# Dashboardtest.net
KiCad netlist of a schematic drawn in EAGLE
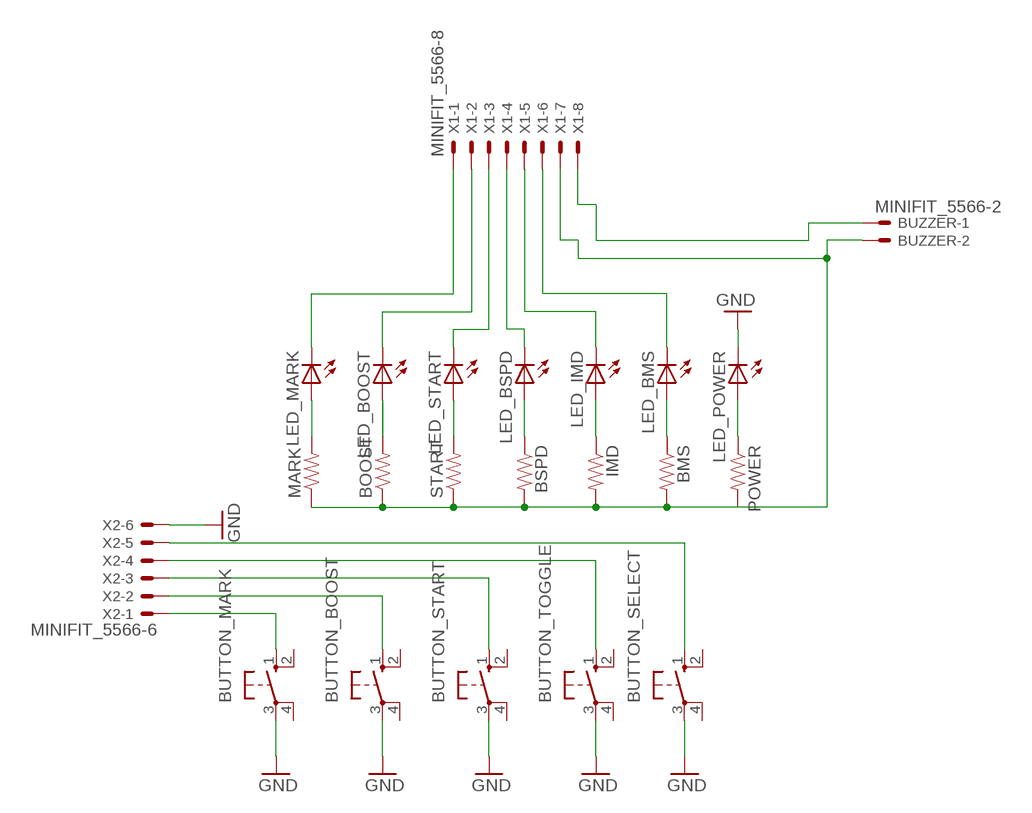
[diagram p0: schematic, sheet 1]

(export (version "E")
  (design (tool "Eeschema 10.0.6"))
  (components
    (comp (ref "BMS")
      (value "RESISTOREZ")
      (footprint "eagle-import:AXIAL-0.3EZ")
      (libsource (lib "eagle-import") (part "RESISTOREZ"))
    )
    (comp (ref "BOOST")
      (value "RESISTOREZ")
      (footprint "eagle-import:AXIAL-0.3EZ")
      (libsource (lib "eagle-import") (part "RESISTOREZ"))
    )
    (comp (ref "BSPD")
      (value "RESISTOREZ")
      (footprint "eagle-import:AXIAL-0.3EZ")
      (libsource (lib "eagle-import") (part "RESISTOREZ"))
    )
    (comp (ref "BUTTON_BOOST")
      (value "BTN_10-XX")
      (footprint "eagle-import:B3F-10XX")
      (fields (field (name "MPN") "B3F-1000"))
      (libsource (lib "eagle-import") (part "BTN_10-XX"))
    )
    (comp (ref "BUTTON_MARK")
      (value "BTN_10-XX")
      (footprint "eagle-import:B3F-10XX")
      (fields (field (name "MPN") "B3F-1000"))
      (libsource (lib "eagle-import") (part "BTN_10-XX"))
    )
    (comp (ref "BUTTON_SELECT")
      (value "BTN_10-XX")
      (footprint "eagle-import:B3F-10XX")
      (fields (field (name "MPN") "B3F-1000"))
      (libsource (lib "eagle-import") (part "BTN_10-XX"))
    )
    (comp (ref "BUTTON_START")
      (value "BTN_10-XX")
      (footprint "eagle-import:B3F-10XX")
      (fields (field (name "MPN") "B3F-1000"))
      (libsource (lib "eagle-import") (part "BTN_10-XX"))
    )
    (comp (ref "BUTTON_TOGGLE")
      (value "BTN_10-XX")
      (footprint "eagle-import:B3F-10XX")
      (fields (field (name "MPN") "B3F-1000"))
      (libsource (lib "eagle-import") (part "BTN_10-XX"))
    )
    (comp (ref "BUZZER")
      (value "MINIFIT_5566-2")
      (footprint "eagle-import:MINIFIT_5566-2")
      (libsource (lib "eagle-import") (part "MINIFIT_5566-2"))
    )
    (comp (ref "IMD")
      (value "RESISTOREZ")
      (footprint "eagle-import:AXIAL-0.3EZ")
      (libsource (lib "eagle-import") (part "RESISTOREZ"))
    )
    (comp (ref "LED_BMS")
      (value "LED-5MM")
      (footprint "eagle-import:LED-5MM")
      (libsource (lib "eagle-import") (part "LED-5MM"))
    )
    (comp (ref "LED_BOOST")
      (value "LED-5MM")
      (footprint "eagle-import:LED-5MM")
      (libsource (lib "eagle-import") (part "LED-5MM"))
    )
    (comp (ref "LED_BSPD")
      (value "LED-5MM")
      (footprint "eagle-import:LED-5MM")
      (libsource (lib "eagle-import") (part "LED-5MM"))
    )
    (comp (ref "LED_IMD")
      (value "LED-5MM")
      (footprint "eagle-import:LED-5MM")
      (libsource (lib "eagle-import") (part "LED-5MM"))
    )
    (comp (ref "LED_MARK")
      (value "LED-5MM")
      (footprint "eagle-import:LED-5MM")
      (libsource (lib "eagle-import") (part "LED-5MM"))
    )
    (comp (ref "LED_POWER")
      (value "LED-5MM")
      (footprint "eagle-import:LED-5MM")
      (libsource (lib "eagle-import") (part "LED-5MM"))
    )
    (comp (ref "LED_START")
      (value "LED-5MM")
      (footprint "eagle-import:LED-5MM")
      (libsource (lib "eagle-import") (part "LED-5MM"))
    )
    (comp (ref "MARK")
      (value "RESISTOREZ")
      (footprint "eagle-import:AXIAL-0.3EZ")
      (libsource (lib "eagle-import") (part "RESISTOREZ"))
    )
    (comp (ref "POWER")
      (value "RESISTOREZ")
      (footprint "eagle-import:AXIAL-0.3EZ")
      (libsource (lib "eagle-import") (part "RESISTOREZ"))
    )
    (comp (ref "START")
      (value "RESISTOREZ")
      (footprint "eagle-import:AXIAL-0.3EZ")
      (libsource (lib "eagle-import") (part "RESISTOREZ"))
    )
    (comp (ref "X1")
      (value "MINIFIT_5566-8")
      (footprint "eagle-import:MINIFIT_5566-8")
      (libsource (lib "eagle-import") (part "MINIFIT_5566-8"))
    )
    (comp (ref "X2")
      (value "MINIFIT_5566-6")
      (footprint "eagle-import:MINIFIT_5566-6")
      (fields (field (name "MPN") "95566-61002"))
      (libsource (lib "eagle-import") (part "MINIFIT_5566-6"))
    )
  )
  (nets
    (net (code "1") (name "GND") (class "Default")
      (node (ref "BUTTON_BOOST") (pin "3") (pinfunction "P_3") (pintype "passive"))
      (node (ref "BUTTON_MARK") (pin "3") (pinfunction "P_3") (pintype "passive"))
      (node (ref "BUTTON_SELECT") (pin "3") (pinfunction "P_3") (pintype "passive"))
      (node (ref "BUTTON_START") (pin "3") (pinfunction "P_3") (pintype "passive"))
      (node (ref "BUTTON_TOGGLE") (pin "3") (pinfunction "P_3") (pintype "passive"))
      (node (ref "LED_POWER") (pin "K") (pinfunction "C_K") (pintype "passive"))
      (node (ref "X2") (pin "6") (pinfunction "S_6") (pintype "passive"))
    )
    (net (code "2") (name "Net-(BMS-1)") (class "Default")
      (node (ref "BMS") (pin "P$1") (pinfunction "1_P$1") (pintype "passive"))
      (node (ref "LED_BMS") (pin "A") (pinfunction "A_A") (pintype "passive"))
    )
    (net (code "3") (name "Net-(BMS-2)") (class "Default")
      (node (ref "BMS") (pin "P$2") (pinfunction "2_P$2") (pintype "passive"))
      (node (ref "BOOST") (pin "P$1") (pinfunction "1_P$1") (pintype "passive"))
      (node (ref "BSPD") (pin "P$2") (pinfunction "2_P$2") (pintype "passive"))
      (node (ref "BUZZER") (pin "2") (pinfunction "S_2") (pintype "passive"))
      (node (ref "IMD") (pin "P$2") (pinfunction "2_P$2") (pintype "passive"))
      (node (ref "MARK") (pin "P$1") (pinfunction "1_P$1") (pintype "passive"))
      (node (ref "POWER") (pin "P$2") (pinfunction "2_P$2") (pintype "passive"))
      (node (ref "START") (pin "P$1") (pinfunction "1_P$1") (pintype "passive"))
      (node (ref "X1") (pin "7") (pinfunction "S_7") (pintype "passive"))
    )
    (net (code "4") (name "Net-(BOOST-2)") (class "Default")
      (node (ref "BOOST") (pin "P$2") (pinfunction "2_P$2") (pintype "passive"))
      (node (ref "LED_BOOST") (pin "A") (pinfunction "A_A") (pintype "passive"))
    )
    (net (code "5") (name "Net-(BSPD-1)") (class "Default")
      (node (ref "BSPD") (pin "P$1") (pinfunction "1_P$1") (pintype "passive"))
      (node (ref "LED_BSPD") (pin "A") (pinfunction "A_A") (pintype "passive"))
    )
    (net (code "6") (name "Net-(BUTTON_BOOST-S)") (class "Default")
      (node (ref "BUTTON_BOOST") (pin "1") (pinfunction "S_1") (pintype "passive"))
      (node (ref "X2") (pin "2") (pinfunction "S_2") (pintype "passive"))
    )
    (net (code "7") (name "Net-(BUTTON_MARK-S)") (class "Default")
      (node (ref "BUTTON_MARK") (pin "1") (pinfunction "S_1") (pintype "passive"))
      (node (ref "X2") (pin "1") (pinfunction "S_1") (pintype "passive"))
    )
    (net (code "8") (name "Net-(BUTTON_SELECT-S)") (class "Default")
      (node (ref "BUTTON_SELECT") (pin "1") (pinfunction "S_1") (pintype "passive"))
      (node (ref "X2") (pin "5") (pinfunction "S_5") (pintype "passive"))
    )
    (net (code "9") (name "Net-(BUTTON_START-S)") (class "Default")
      (node (ref "BUTTON_START") (pin "1") (pinfunction "S_1") (pintype "passive"))
      (node (ref "X2") (pin "3") (pinfunction "S_3") (pintype "passive"))
    )
    (net (code "10") (name "Net-(BUTTON_TOGGLE-S)") (class "Default")
      (node (ref "BUTTON_TOGGLE") (pin "1") (pinfunction "S_1") (pintype "passive"))
      (node (ref "X2") (pin "4") (pinfunction "S_4") (pintype "passive"))
    )
    (net (code "11") (name "Net-(BUZZERA-S)") (class "Default")
      (node (ref "BUZZER") (pin "1") (pinfunction "S_1") (pintype "passive"))
      (node (ref "X1") (pin "8") (pinfunction "S_8") (pintype "passive"))
    )
    (net (code "12") (name "Net-(IMD-1)") (class "Default")
      (node (ref "IMD") (pin "P$1") (pinfunction "1_P$1") (pintype "passive"))
      (node (ref "LED_IMD") (pin "A") (pinfunction "A_A") (pintype "passive"))
    )
    (net (code "13") (name "Net-(LED_BMS-C)") (class "Default")
      (node (ref "LED_BMS") (pin "K") (pinfunction "C_K") (pintype "passive"))
      (node (ref "X1") (pin "6") (pinfunction "S_6") (pintype "passive"))
    )
    (net (code "14") (name "Net-(LED_BOOST-C)") (class "Default")
      (node (ref "LED_BOOST") (pin "K") (pinfunction "C_K") (pintype "passive"))
      (node (ref "X1") (pin "2") (pinfunction "S_2") (pintype "passive"))
    )
    (net (code "15") (name "Net-(LED_BSPD-C)") (class "Default")
      (node (ref "LED_BSPD") (pin "K") (pinfunction "C_K") (pintype "passive"))
      (node (ref "X1") (pin "4") (pinfunction "S_4") (pintype "passive"))
    )
    (net (code "16") (name "Net-(LED_IMD-C)") (class "Default")
      (node (ref "LED_IMD") (pin "K") (pinfunction "C_K") (pintype "passive"))
      (node (ref "X1") (pin "5") (pinfunction "S_5") (pintype "passive"))
    )
    (net (code "17") (name "Net-(LED_MARK-C)") (class "Default")
      (node (ref "LED_MARK") (pin "K") (pinfunction "C_K") (pintype "passive"))
      (node (ref "X1") (pin "1") (pinfunction "S_1") (pintype "passive"))
    )
    (net (code "18") (name "Net-(LED_START-C)") (class "Default")
      (node (ref "LED_START") (pin "K") (pinfunction "C_K") (pintype "passive"))
      (node (ref "X1") (pin "3") (pinfunction "S_3") (pintype "passive"))
    )
    (net (code "19") (name "Net-(MARK-2)") (class "Default")
      (node (ref "LED_MARK") (pin "A") (pinfunction "A_A") (pintype "passive"))
      (node (ref "MARK") (pin "P$2") (pinfunction "2_P$2") (pintype "passive"))
    )
    (net (code "20") (name "Net-(POWER-1)") (class "Default")
      (node (ref "LED_POWER") (pin "A") (pinfunction "A_A") (pintype "passive"))
      (node (ref "POWER") (pin "P$1") (pinfunction "1_P$1") (pintype "passive"))
    )
    (net (code "21") (name "Net-(START-2)") (class "Default")
      (node (ref "LED_START") (pin "A") (pinfunction "A_A") (pintype "passive"))
      (node (ref "START") (pin "P$2") (pinfunction "2_P$2") (pintype "passive"))
    )
    (net (code "22") (name "unconnected-(BUTTON_BOOST-P1-Pad4)") (class "Default")
      (node (ref "BUTTON_BOOST") (pin "4") (pinfunction "P1_4") (pintype "passive"))
    )
    (net (code "23") (name "unconnected-(BUTTON_BOOST-S1-Pad2)") (class "Default")
      (node (ref "BUTTON_BOOST") (pin "2") (pinfunction "S1_2") (pintype "passive"))
    )
    (net (code "24") (name "unconnected-(BUTTON_MARK-P1-Pad4)") (class "Default")
      (node (ref "BUTTON_MARK") (pin "4") (pinfunction "P1_4") (pintype "passive"))
    )
    (net (code "25") (name "unconnected-(BUTTON_MARK-S1-Pad2)") (class "Default")
      (node (ref "BUTTON_MARK") (pin "2") (pinfunction "S1_2") (pintype "passive"))
    )
    (net (code "26") (name "unconnected-(BUTTON_SELECT-P1-Pad4)") (class "Default")
      (node (ref "BUTTON_SELECT") (pin "4") (pinfunction "P1_4") (pintype "passive"))
    )
    (net (code "27") (name "unconnected-(BUTTON_SELECT-S1-Pad2)") (class "Default")
      (node (ref "BUTTON_SELECT") (pin "2") (pinfunction "S1_2") (pintype "passive"))
    )
    (net (code "28") (name "unconnected-(BUTTON_START-P1-Pad4)") (class "Default")
      (node (ref "BUTTON_START") (pin "4") (pinfunction "P1_4") (pintype "passive"))
    )
    (net (code "29") (name "unconnected-(BUTTON_START-S1-Pad2)") (class "Default")
      (node (ref "BUTTON_START") (pin "2") (pinfunction "S1_2") (pintype "passive"))
    )
    (net (code "30") (name "unconnected-(BUTTON_TOGGLE-P1-Pad4)") (class "Default")
      (node (ref "BUTTON_TOGGLE") (pin "4") (pinfunction "P1_4") (pintype "passive"))
    )
    (net (code "31") (name "unconnected-(BUTTON_TOGGLE-S1-Pad2)") (class "Default")
      (node (ref "BUTTON_TOGGLE") (pin "2") (pinfunction "S1_2") (pintype "passive"))
    )
  )
)
